# IN-1_Module.net
KiCad netlist of a schematic drawn in EAGLE
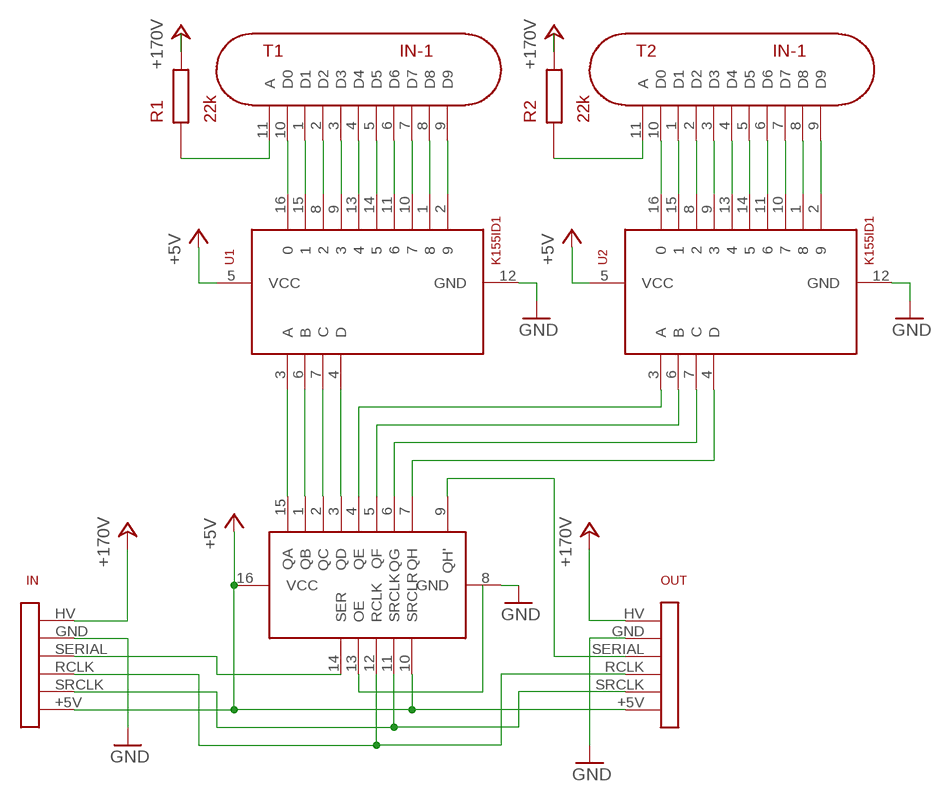
[diagram p0: schematic, sheet 1]

(export (version "E")
  (design (tool "Eeschema 10.0.6"))
  (components
    (comp (ref "IN")
      (value "NIXIE_INTERCONNECT")
      (footprint "eagle-import:NIXIE_INTERCONNECT")
      (libsource (lib "eagle-import") (part "NIXIE_INTERCONNECT"))
    )
    (comp (ref "OUT")
      (value "NIXIE_INTERCONNECT")
      (footprint "eagle-import:NIXIE_INTERCONNECT")
      (libsource (lib "eagle-import") (part "NIXIE_INTERCONNECT"))
    )
    (comp (ref "R1")
      (value "22k")
      (footprint "eagle-import:ANODE_RESISTOR")
      (libsource (lib "eagle-import") (part "ANODE_RESISTOR"))
    )
    (comp (ref "R2")
      (value "22k")
      (footprint "eagle-import:ANODE_RESISTOR")
      (libsource (lib "eagle-import") (part "ANODE_RESISTOR"))
    )
    (comp (ref "T1")
      (value "IN-1")
      (footprint "eagle-import:IN-1")
      (libsource (lib "eagle-import") (part "IN-1"))
    )
    (comp (ref "T2")
      (value "IN-1")
      (footprint "eagle-import:IN-1")
      (libsource (lib "eagle-import") (part "IN-1"))
    )
    (comp (ref "U1")
      (value "K155ID1")
      (footprint "eagle-import:DIP16-2.54-19.2X7.62MM")
      (libsource (lib "eagle-import") (part "K155ID1"))
    )
    (comp (ref "U2")
      (value "K155ID1")
      (footprint "eagle-import:DIP16-2.54-19.2X7.62MM")
      (libsource (lib "eagle-import") (part "K155ID1"))
    )
    (comp (ref "U3")
      (value "74HC595")
      (footprint "eagle-import:DIL16")
      (libsource (lib "eagle-import") (part "74HC595"))
    )
  )
  (nets
    (net (code "1") (name "+5V") (class "Default")
      (node (ref "IN") (pin "+5V") (pinfunction "+5V_+5V") (pintype "bidirectional"))
      (node (ref "OUT") (pin "+5V") (pinfunction "+5V_+5V") (pintype "bidirectional"))
      (node (ref "U1") (pin "5") (pinfunction "VCC_5") (pintype "bidirectional"))
      (node (ref "U2") (pin "5") (pinfunction "VCC_5") (pintype "bidirectional"))
      (node (ref "U3") (pin "10") (pinfunction "SRCLR_10") (pintype "bidirectional"))
      (node (ref "U3") (pin "16") (pinfunction "VCC_16") (pintype "bidirectional"))
    )
    (net (code "2") (name "+170V") (class "Default")
      (node (ref "IN") (pin "HV") (pinfunction "HV_HV") (pintype "bidirectional"))
      (node (ref "OUT") (pin "HV") (pinfunction "HV_HV") (pintype "bidirectional"))
      (node (ref "R1") (pin "P$2") (pinfunction "P$2_P$2") (pintype "bidirectional"))
      (node (ref "R2") (pin "P$2") (pinfunction "P$2_P$2") (pintype "bidirectional"))
    )
    (net (code "3") (name "GND") (class "Default")
      (node (ref "IN") (pin "GND") (pinfunction "GND_GND") (pintype "bidirectional"))
      (node (ref "OUT") (pin "GND") (pinfunction "GND_GND") (pintype "bidirectional"))
      (node (ref "U1") (pin "12") (pinfunction "GND_12") (pintype "bidirectional"))
      (node (ref "U2") (pin "12") (pinfunction "GND_12") (pintype "bidirectional"))
      (node (ref "U3") (pin "8") (pinfunction "GND_8") (pintype "bidirectional"))
    )
    (net (code "4") (name "Net-(T1-A)") (class "Default")
      (node (ref "R1") (pin "P$1") (pinfunction "P$1_P$1") (pintype "bidirectional"))
      (node (ref "T1") (pin "11") (pinfunction "A_11") (pintype "bidirectional"))
    )
    (net (code "5") (name "Net-(T1-D0)") (class "Default")
      (node (ref "T1") (pin "10") (pinfunction "D0_10") (pintype "bidirectional"))
      (node (ref "U1") (pin "16") (pinfunction "0_16") (pintype "bidirectional"))
    )
    (net (code "6") (name "Net-(T1-D1)") (class "Default")
      (node (ref "T1") (pin "1") (pinfunction "D1_1") (pintype "bidirectional"))
      (node (ref "U1") (pin "15") (pinfunction "1_15") (pintype "bidirectional"))
    )
    (net (code "7") (name "Net-(T1-D2)") (class "Default")
      (node (ref "T1") (pin "2") (pinfunction "D2_2") (pintype "bidirectional"))
      (node (ref "U1") (pin "8") (pinfunction "2_8") (pintype "bidirectional"))
    )
    (net (code "8") (name "Net-(T1-D3)") (class "Default")
      (node (ref "T1") (pin "3") (pinfunction "D3_3") (pintype "bidirectional"))
      (node (ref "U1") (pin "9") (pinfunction "3_9") (pintype "bidirectional"))
    )
    (net (code "9") (name "Net-(T1-D4)") (class "Default")
      (node (ref "T1") (pin "4") (pinfunction "D4_4") (pintype "bidirectional"))
      (node (ref "U1") (pin "13") (pinfunction "4_13") (pintype "bidirectional"))
    )
    (net (code "10") (name "Net-(T1-D5)") (class "Default")
      (node (ref "T1") (pin "5") (pinfunction "D5_5") (pintype "bidirectional"))
      (node (ref "U1") (pin "14") (pinfunction "5_14") (pintype "bidirectional"))
    )
    (net (code "11") (name "Net-(T1-D6)") (class "Default")
      (node (ref "T1") (pin "6") (pinfunction "D6_6") (pintype "bidirectional"))
      (node (ref "U1") (pin "11") (pinfunction "6_11") (pintype "bidirectional"))
    )
    (net (code "12") (name "Net-(T1-D7)") (class "Default")
      (node (ref "T1") (pin "7") (pinfunction "D7_7") (pintype "bidirectional"))
      (node (ref "U1") (pin "10") (pinfunction "7_10") (pintype "bidirectional"))
    )
    (net (code "13") (name "Net-(T1-D8)") (class "Default")
      (node (ref "T1") (pin "8") (pinfunction "D8_8") (pintype "bidirectional"))
      (node (ref "U1") (pin "1") (pinfunction "8_1") (pintype "bidirectional"))
    )
    (net (code "14") (name "Net-(T1-D9)") (class "Default")
      (node (ref "T1") (pin "9") (pinfunction "D9_9") (pintype "bidirectional"))
      (node (ref "U1") (pin "2") (pinfunction "9_2") (pintype "bidirectional"))
    )
    (net (code "15") (name "Net-(T2-A)") (class "Default")
      (node (ref "R2") (pin "P$1") (pinfunction "P$1_P$1") (pintype "bidirectional"))
      (node (ref "T2") (pin "11") (pinfunction "A_11") (pintype "bidirectional"))
    )
    (net (code "16") (name "Net-(T2-D0)") (class "Default")
      (node (ref "T2") (pin "10") (pinfunction "D0_10") (pintype "bidirectional"))
      (node (ref "U2") (pin "16") (pinfunction "0_16") (pintype "bidirectional"))
    )
    (net (code "17") (name "Net-(T2-D1)") (class "Default")
      (node (ref "T2") (pin "1") (pinfunction "D1_1") (pintype "bidirectional"))
      (node (ref "U2") (pin "15") (pinfunction "1_15") (pintype "bidirectional"))
    )
    (net (code "18") (name "Net-(T2-D2)") (class "Default")
      (node (ref "T2") (pin "2") (pinfunction "D2_2") (pintype "bidirectional"))
      (node (ref "U2") (pin "8") (pinfunction "2_8") (pintype "bidirectional"))
    )
    (net (code "19") (name "Net-(T2-D3)") (class "Default")
      (node (ref "T2") (pin "3") (pinfunction "D3_3") (pintype "bidirectional"))
      (node (ref "U2") (pin "9") (pinfunction "3_9") (pintype "bidirectional"))
    )
    (net (code "20") (name "Net-(T2-D4)") (class "Default")
      (node (ref "T2") (pin "4") (pinfunction "D4_4") (pintype "bidirectional"))
      (node (ref "U2") (pin "13") (pinfunction "4_13") (pintype "bidirectional"))
    )
    (net (code "21") (name "Net-(T2-D5)") (class "Default")
      (node (ref "T2") (pin "5") (pinfunction "D5_5") (pintype "bidirectional"))
      (node (ref "U2") (pin "14") (pinfunction "5_14") (pintype "bidirectional"))
    )
    (net (code "22") (name "Net-(T2-D6)") (class "Default")
      (node (ref "T2") (pin "6") (pinfunction "D6_6") (pintype "bidirectional"))
      (node (ref "U2") (pin "11") (pinfunction "6_11") (pintype "bidirectional"))
    )
    (net (code "23") (name "Net-(T2-D7)") (class "Default")
      (node (ref "T2") (pin "7") (pinfunction "D7_7") (pintype "bidirectional"))
      (node (ref "U2") (pin "10") (pinfunction "7_10") (pintype "bidirectional"))
    )
    (net (code "24") (name "Net-(T2-D8)") (class "Default")
      (node (ref "T2") (pin "8") (pinfunction "D8_8") (pintype "bidirectional"))
      (node (ref "U2") (pin "1") (pinfunction "8_1") (pintype "bidirectional"))
    )
    (net (code "25") (name "Net-(T2-D9)") (class "Default")
      (node (ref "T2") (pin "9") (pinfunction "D9_9") (pintype "bidirectional"))
      (node (ref "U2") (pin "2") (pinfunction "9_2") (pintype "bidirectional"))
    )
    (net (code "26") (name "Net-(U1-A)") (class "Default")
      (node (ref "U1") (pin "3") (pinfunction "A_3") (pintype "bidirectional"))
      (node (ref "U3") (pin "15") (pinfunction "QA_15") (pintype "bidirectional"))
    )
    (net (code "27") (name "Net-(U1-B)") (class "Default")
      (node (ref "U1") (pin "6") (pinfunction "B_6") (pintype "bidirectional"))
      (node (ref "U3") (pin "1") (pinfunction "QB_1") (pintype "bidirectional"))
    )
    (net (code "28") (name "Net-(U1-C)") (class "Default")
      (node (ref "U1") (pin "7") (pinfunction "C_7") (pintype "bidirectional"))
      (node (ref "U3") (pin "2") (pinfunction "QC_2") (pintype "bidirectional"))
    )
    (net (code "29") (name "Net-(U1-D)") (class "Default")
      (node (ref "U1") (pin "4") (pinfunction "D_4") (pintype "bidirectional"))
      (node (ref "U3") (pin "3") (pinfunction "QD_3") (pintype "bidirectional"))
    )
    (net (code "30") (name "Net-(U2-A)") (class "Default")
      (node (ref "U2") (pin "3") (pinfunction "A_3") (pintype "bidirectional"))
      (node (ref "U3") (pin "4") (pinfunction "QE_4") (pintype "bidirectional"))
    )
    (net (code "31") (name "Net-(U2-B)") (class "Default")
      (node (ref "U2") (pin "6") (pinfunction "B_6") (pintype "bidirectional"))
      (node (ref "U3") (pin "5") (pinfunction "QF_5") (pintype "bidirectional"))
    )
    (net (code "32") (name "Net-(U2-C)") (class "Default")
      (node (ref "U2") (pin "7") (pinfunction "C_7") (pintype "bidirectional"))
      (node (ref "U3") (pin "6") (pinfunction "QG_6") (pintype "bidirectional"))
    )
    (net (code "33") (name "Net-(U2-D)") (class "Default")
      (node (ref "U2") (pin "4") (pinfunction "D_4") (pintype "bidirectional"))
      (node (ref "U3") (pin "7") (pinfunction "QH_7") (pintype "bidirectional"))
    )
    (net (code "34") (name "Net-(U3-QH')") (class "Default")
      (node (ref "OUT") (pin "SERIAL") (pinfunction "SERIAL_SERIAL") (pintype "bidirectional"))
      (node (ref "U3") (pin "9") (pinfunction "QH'_9") (pintype "bidirectional"))
    )
    (net (code "35") (name "Net-(U3-RCLK)") (class "Default")
      (node (ref "IN") (pin "RCLK") (pinfunction "RCLK_RCLK") (pintype "bidirectional"))
      (node (ref "OUT") (pin "RCLK") (pinfunction "RCLK_RCLK") (pintype "bidirectional"))
      (node (ref "U3") (pin "12") (pinfunction "RCLK_12") (pintype "bidirectional"))
    )
    (net (code "36") (name "Net-(U3-SER)") (class "Default")
      (node (ref "IN") (pin "SERIAL") (pinfunction "SERIAL_SERIAL") (pintype "bidirectional"))
      (node (ref "U3") (pin "14") (pinfunction "SER_14") (pintype "bidirectional"))
    )
    (net (code "37") (name "Net-(U3-SRCLK)") (class "Default")
      (node (ref "IN") (pin "SRCLK") (pinfunction "SRCLK_SRCLK") (pintype "bidirectional"))
      (node (ref "OUT") (pin "SRCLK") (pinfunction "SRCLK_SRCLK") (pintype "bidirectional"))
      (node (ref "U3") (pin "11") (pinfunction "SRCLK_11") (pintype "bidirectional"))
    )
    (net (code "38") (name "unconnected-(U3-OE-Pad13)") (class "Default")
      (node (ref "U3") (pin "13") (pinfunction "OE_13") (pintype "bidirectional"))
    )
  )
)
